# EagleCAD_tutorial.net
KiCad netlist of a schematic drawn in EAGLE
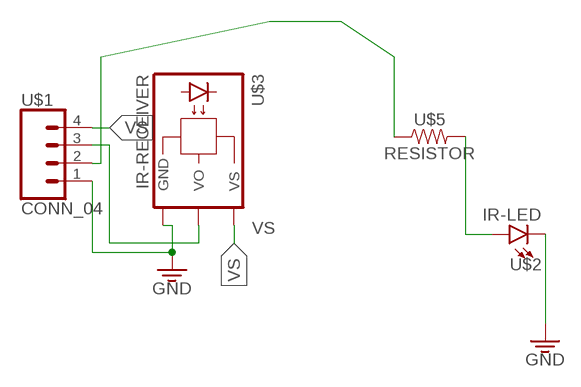
[diagram p0: schematic, sheet 1]

(export (version "E")
  (design (tool "Eeschema 10.0.6"))
  (components
    (comp (ref "U$1")
      (value "CONN_04")
      (footprint "eagle-import:MOLEX-1X4")
      (libsource (lib "eagle-import") (part "CONN_04"))
    )
    (comp (ref "U$2")
      (value "IR-LED")
      (footprint "eagle-import:LED_5MM")
      (libsource (lib "eagle-import") (part "IR-LED"))
    )
    (comp (ref "U$3")
      (value "IR-RECEIVER")
      (footprint "eagle-import:TSOP17_TB1")
      (libsource (lib "eagle-import") (part "IR-RECEIVER"))
    )
    (comp (ref "U$5")
      (value "RESISTOR")
      (footprint "eagle-import:AXIAL-0.3")
      (libsource (lib "eagle-import") (part "RESISTOR"))
    )
  )
  (nets
    (net (code "1") (name "GND") (class "Default")
      (node (ref "U$1") (pin "1") (pinfunction "1_1") (pintype "passive"))
      (node (ref "U$2") (pin "K") (pinfunction "C_K") (pintype "passive"))
      (node (ref "U$3") (pin "GND") (pinfunction "GND_GND") (pintype "bidirectional"))
    )
    (net (code "2") (name "Net-(U$1-Pad3)") (class "Default")
      (node (ref "U$1") (pin "3") (pinfunction "3_3") (pintype "passive"))
      (node (ref "U$3") (pin "VO") (pinfunction "VO_VO") (pintype "open_collector"))
    )
    (net (code "3") (name "Net-(U$5-1)") (class "Default")
      (node (ref "U$1") (pin "2") (pinfunction "2_2") (pintype "passive"))
      (node (ref "U$5") (pin "P$1") (pinfunction "1_P$1") (pintype "passive"))
    )
    (net (code "4") (name "Net-(U$5-2)") (class "Default")
      (node (ref "U$2") (pin "A") (pinfunction "A_A") (pintype "passive"))
      (node (ref "U$5") (pin "P$2") (pinfunction "2_P$2") (pintype "passive"))
    )
    (net (code "5") (name "VS") (class "Default")
      (node (ref "U$1") (pin "4") (pinfunction "4_4") (pintype "passive"))
      (node (ref "U$3") (pin "VS") (pinfunction "VS_VS") (pintype "bidirectional"))
    )
  )
)
